# power_amp4.net
KiCad netlist of a schematic drawn in EAGLE
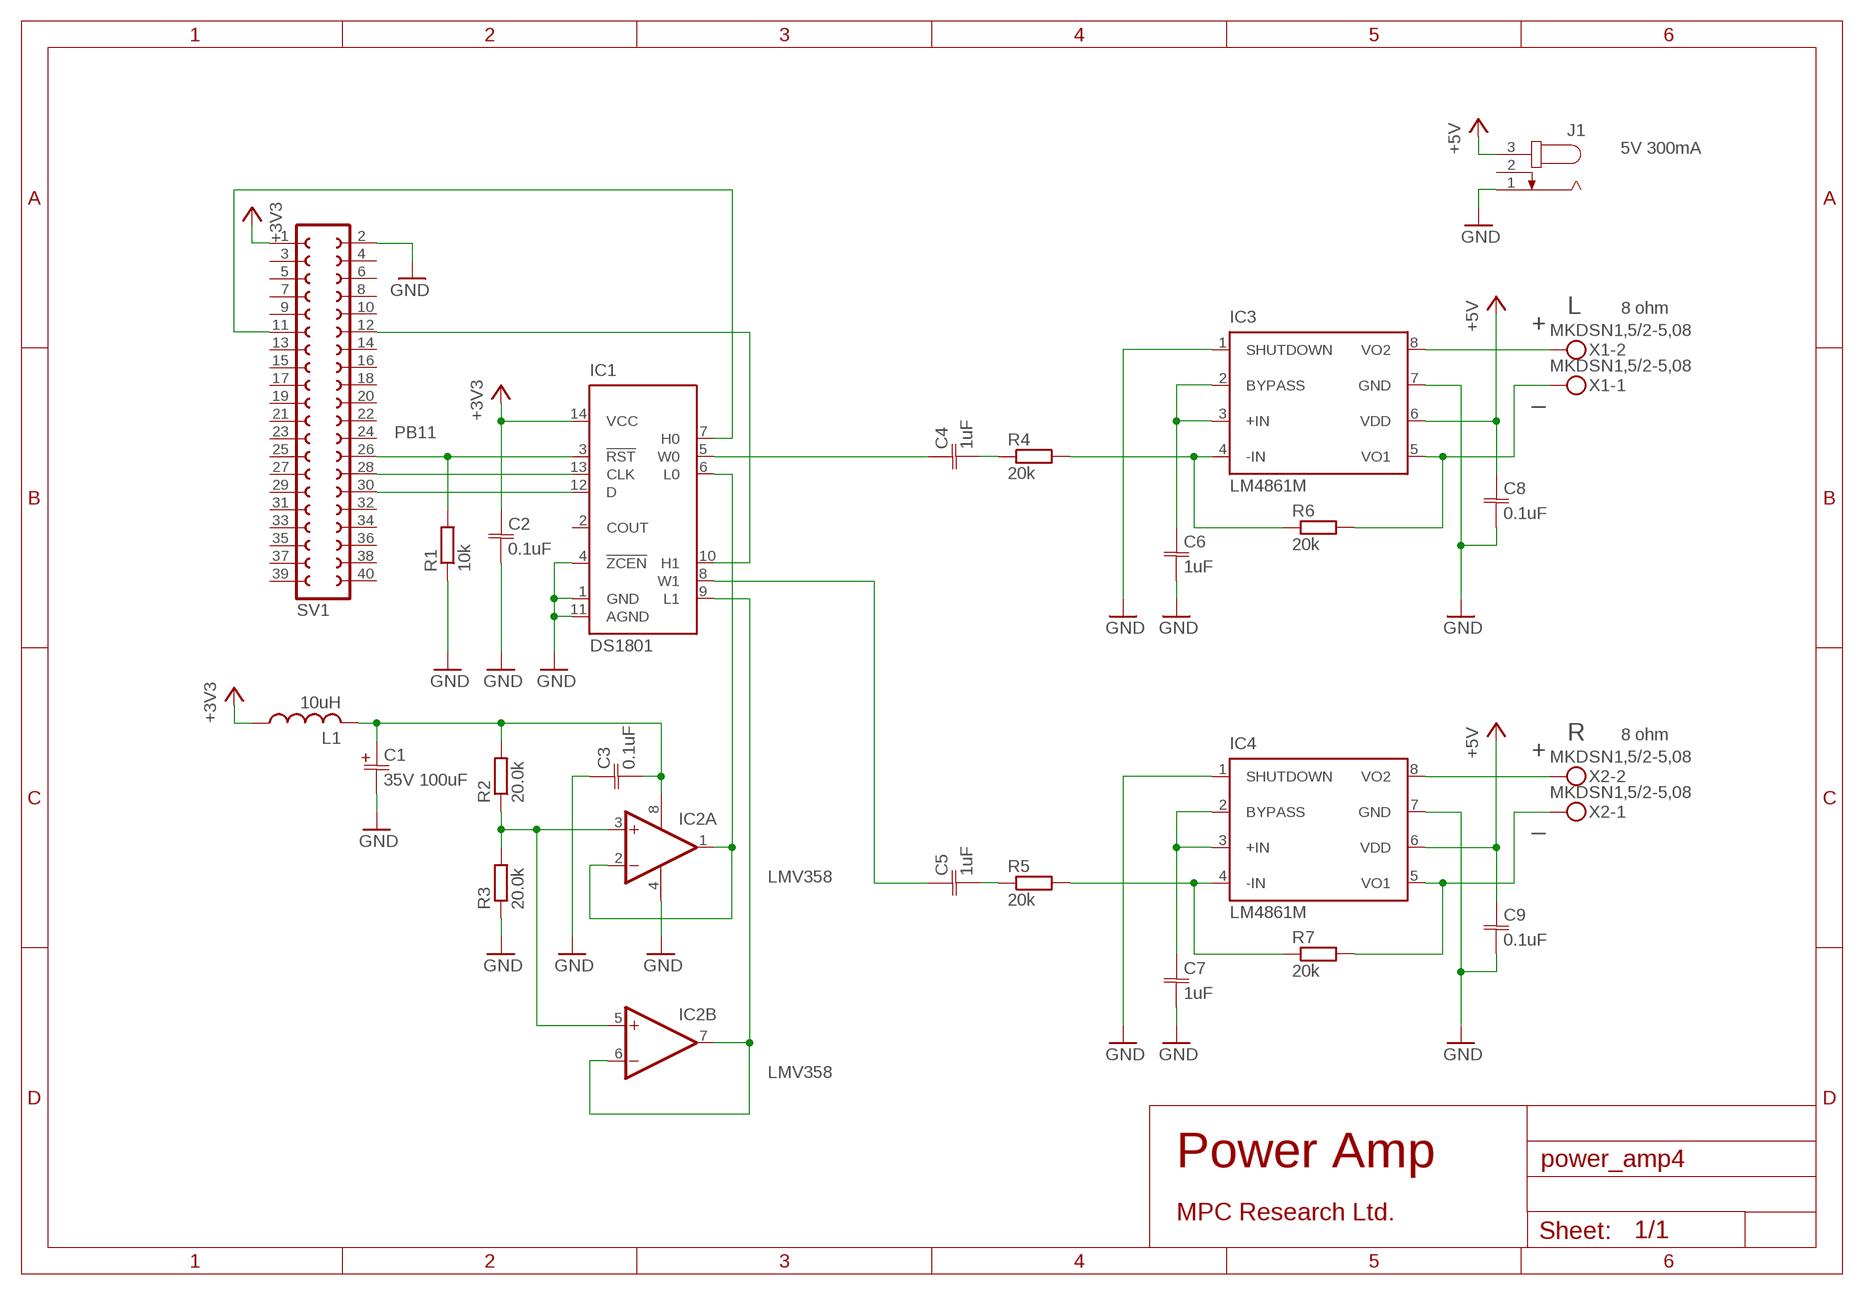
[diagram p0: schematic, sheet 1]

(export (version "E")
  (design (tool "Eeschema 10.0.6"))
  (components
    (comp (ref "C1")
      (value "35V 100uF")
      (footprint "eagle-import:E2,5-5")
      (libsource (lib "eagle-import") (part "CPOL-JIS"))
    )
    (comp (ref "C2")
      (value "0.1uF")
      (footprint "eagle-import:C050-024X044")
      (libsource (lib "eagle-import") (part "C-JIS050-024X044"))
    )
    (comp (ref "C3")
      (value "0.1uF")
      (footprint "eagle-import:C050-024X044")
      (libsource (lib "eagle-import") (part "C-JIS050-024X044"))
    )
    (comp (ref "C4")
      (value "1uF")
      (footprint "eagle-import:C050-024X044")
      (libsource (lib "eagle-import") (part "C-JIS050-024X044"))
    )
    (comp (ref "C5")
      (value "1uF")
      (footprint "eagle-import:C050-024X044")
      (libsource (lib "eagle-import") (part "C-JIS050-024X044"))
    )
    (comp (ref "C6")
      (value "1uF")
      (footprint "eagle-import:C050-024X044")
      (libsource (lib "eagle-import") (part "C-JIS050-024X044"))
    )
    (comp (ref "C7")
      (value "1uF")
      (footprint "eagle-import:C050-024X044")
      (libsource (lib "eagle-import") (part "C-JIS050-024X044"))
    )
    (comp (ref "C8")
      (value "0.1uF")
      (footprint "eagle-import:C050-024X044")
      (libsource (lib "eagle-import") (part "C-JIS050-024X044"))
    )
    (comp (ref "C9")
      (value "0.1uF")
      (footprint "eagle-import:C050-024X044")
      (libsource (lib "eagle-import") (part "C-JIS050-024X044"))
    )
    (comp (ref "IC1")
      (value "DS1801")
      (footprint "eagle-import:DIL14")
      (libsource (lib "eagle-import") (part "DS1801"))
    )
    (comp (ref "IC2")
      (value "LMV358")
      (footprint "eagle-import:SO08")
      (libsource (lib "eagle-import") (part "LMV358?M"))
    )
    (comp (ref "IC3")
      (value "LM4861M")
      (footprint "eagle-import:SO-08")
      (libsource (lib "eagle-import") (part "LM4861M"))
    )
    (comp (ref "IC4")
      (value "LM4861M")
      (footprint "eagle-import:SO-08")
      (libsource (lib "eagle-import") (part "LM4861M"))
    )
    (comp (ref "J1")
      (value "JACK-PLUG0")
      (footprint "eagle-import:SPC4077")
      (libsource (lib "eagle-import") (part "JACK-PLUG0"))
    )
    (comp (ref "L1")
      (value "10uH")
      (footprint "eagle-import:0207_10")
      (libsource (lib "eagle-import") (part "L-US0207/10"))
    )
    (comp (ref "R1")
      (value "10k")
      (footprint "eagle-import:0207_10")
      (libsource (lib "eagle-import") (part "R-EU_0207/10"))
    )
    (comp (ref "R2")
      (value "20.0k")
      (footprint "eagle-import:0207_10")
      (libsource (lib "eagle-import") (part "R-EU_0207/10"))
    )
    (comp (ref "R3")
      (value "20.0k")
      (footprint "eagle-import:0207_10")
      (libsource (lib "eagle-import") (part "R-EU_0207/10"))
    )
    (comp (ref "R4")
      (value "20k")
      (footprint "eagle-import:0207_10")
      (libsource (lib "eagle-import") (part "R-EU_0207/10"))
    )
    (comp (ref "R5")
      (value "20k")
      (footprint "eagle-import:0207_10")
      (libsource (lib "eagle-import") (part "R-EU_0207/10"))
    )
    (comp (ref "R6")
      (value "20k")
      (footprint "eagle-import:0207_10")
      (libsource (lib "eagle-import") (part "R-EU_0207/10"))
    )
    (comp (ref "R7")
      (value "20k")
      (footprint "eagle-import:0207_10")
      (libsource (lib "eagle-import") (part "R-EU_0207/10"))
    )
    (comp (ref "SV1")
      (value "FE20-2")
      (footprint "eagle-import:FE20-2")
      (libsource (lib "eagle-import") (part "FE20-2"))
    )
    (comp (ref "X1")
      (value "MKDSN1,5/2-5,08")
      (footprint "eagle-import:MKDSN1,5_2-5,08")
      (fields (field (name "MPN") "MKDSN 1,5/2-5.08"))
      (libsource (lib "eagle-import") (part "MKDSN1,5/2-5,08"))
    )
    (comp (ref "X2")
      (value "MKDSN1,5/2-5,08")
      (footprint "eagle-import:MKDSN1,5_2-5,08")
      (fields (field (name "MPN") "MKDSN 1,5/2-5.08"))
      (libsource (lib "eagle-import") (part "MKDSN1,5/2-5,08"))
    )
  )
  (nets
    (net (code "1") (name "+3V3") (class "Default")
      (node (ref "C2") (pin "1") (pinfunction "1_1") (pintype "passive"))
      (node (ref "IC1") (pin "14") (pinfunction "VCC_14") (pintype "power_in"))
      (node (ref "L1") (pin "1") (pinfunction "1_1") (pintype "passive"))
      (node (ref "SV1") (pin "1") (pinfunction "1_1") (pintype "passive"))
    )
    (net (code "2") (name "+5V") (class "Default")
      (node (ref "C8") (pin "1") (pinfunction "1_1") (pintype "passive"))
      (node (ref "C9") (pin "1") (pinfunction "1_1") (pintype "passive"))
      (node (ref "IC3") (pin "6") (pinfunction "VDD_6") (pintype "power_in"))
      (node (ref "IC4") (pin "6") (pinfunction "VDD_6") (pintype "power_in"))
      (node (ref "J1") (pin "3") (pinfunction "3_3") (pintype "passive"))
    )
    (net (code "3") (name "GND") (class "Default")
      (node (ref "C1") (pin "-") (pinfunction "-_-") (pintype "passive"))
      (node (ref "C2") (pin "2") (pinfunction "2_2") (pintype "passive"))
      (node (ref "C3") (pin "1") (pinfunction "1_1") (pintype "passive"))
      (node (ref "C6") (pin "2") (pinfunction "2_2") (pintype "passive"))
      (node (ref "C7") (pin "2") (pinfunction "2_2") (pintype "passive"))
      (node (ref "C8") (pin "2") (pinfunction "2_2") (pintype "passive"))
      (node (ref "C9") (pin "2") (pinfunction "2_2") (pintype "passive"))
      (node (ref "IC1") (pin "1") (pinfunction "GND_1") (pintype "power_in"))
      (node (ref "IC1") (pin "11") (pinfunction "AGND_11") (pintype "power_in"))
      (node (ref "IC1") (pin "4") (pinfunction "~{ZCEN}_4") (pintype "input"))
      (node (ref "IC2") (pin "4") (pinfunction "V-_4") (pintype "power_in"))
      (node (ref "IC3") (pin "1") (pinfunction "SHUTDOWN_1") (pintype "input"))
      (node (ref "IC3") (pin "7") (pinfunction "GND_7") (pintype "power_in"))
      (node (ref "IC4") (pin "1") (pinfunction "SHUTDOWN_1") (pintype "input"))
      (node (ref "IC4") (pin "7") (pinfunction "GND_7") (pintype "power_in"))
      (node (ref "J1") (pin "1") (pinfunction "1_1") (pintype "passive"))
      (node (ref "R1") (pin "1") (pinfunction "1_1") (pintype "passive"))
      (node (ref "R3") (pin "1") (pinfunction "1_1") (pintype "passive"))
      (node (ref "SV1") (pin "2") (pinfunction "2_2") (pintype "passive"))
    )
    (net (code "4") (name "Net-(C4-Pad2)") (class "Default")
      (node (ref "C4") (pin "2") (pinfunction "2_2") (pintype "passive"))
      (node (ref "R4") (pin "1") (pinfunction "1_1") (pintype "passive"))
    )
    (net (code "5") (name "Net-(C5-Pad2)") (class "Default")
      (node (ref "C5") (pin "2") (pinfunction "2_2") (pintype "passive"))
      (node (ref "R5") (pin "1") (pinfunction "1_1") (pintype "passive"))
    )
    (net (code "6") (name "Net-(IC1-CLK)") (class "Default")
      (node (ref "IC1") (pin "13") (pinfunction "CLK_13") (pintype "input"))
      (node (ref "SV1") (pin "28") (pinfunction "28_28") (pintype "passive"))
    )
    (net (code "7") (name "Net-(IC1-D)") (class "Default")
      (node (ref "IC1") (pin "12") (pinfunction "D_12") (pintype "input"))
      (node (ref "SV1") (pin "30") (pinfunction "30_30") (pintype "passive"))
    )
    (net (code "8") (name "Net-(IC1-H0)") (class "Default")
      (node (ref "IC1") (pin "7") (pinfunction "H0_7") (pintype "passive"))
      (node (ref "SV1") (pin "11") (pinfunction "11_11") (pintype "passive"))
    )
    (net (code "9") (name "Net-(IC1-H1)") (class "Default")
      (node (ref "IC1") (pin "10") (pinfunction "H1_10") (pintype "passive"))
      (node (ref "SV1") (pin "12") (pinfunction "12_12") (pintype "passive"))
    )
    (net (code "10") (name "Net-(IC1-L0)") (class "Default")
      (node (ref "IC1") (pin "6") (pinfunction "L0_6") (pintype "passive"))
      (node (ref "IC2") (pin "1") (pinfunction "OUT_1") (pintype "output"))
      (node (ref "IC2") (pin "2") (pinfunction "-IN_2") (pintype "input"))
    )
    (net (code "11") (name "Net-(IC1-L1)") (class "Default")
      (node (ref "IC1") (pin "9") (pinfunction "L1_9") (pintype "passive"))
      (node (ref "IC2") (pin "6") (pinfunction "-IN_6") (pintype "input"))
      (node (ref "IC2") (pin "7") (pinfunction "OUT_7") (pintype "output"))
    )
    (net (code "12") (name "Net-(IC1-W0)") (class "Default")
      (node (ref "C4") (pin "1") (pinfunction "1_1") (pintype "passive"))
      (node (ref "IC1") (pin "5") (pinfunction "W0_5") (pintype "passive"))
    )
    (net (code "13") (name "Net-(IC1-W1)") (class "Default")
      (node (ref "C5") (pin "1") (pinfunction "1_1") (pintype "passive"))
      (node (ref "IC1") (pin "8") (pinfunction "W1_8") (pintype "passive"))
    )
    (net (code "14") (name "Net-(IC1-~{RST})") (class "Default")
      (node (ref "IC1") (pin "3") (pinfunction "~{RST}_3") (pintype "input"))
      (node (ref "R1") (pin "2") (pinfunction "2_2") (pintype "passive"))
      (node (ref "SV1") (pin "26") (pinfunction "26_26") (pintype "passive"))
    )
    (net (code "15") (name "Net-(IC2A-+IN)") (class "Default")
      (node (ref "IC2") (pin "3") (pinfunction "+IN_3") (pintype "input"))
      (node (ref "IC2") (pin "5") (pinfunction "+IN_5") (pintype "input"))
      (node (ref "R2") (pin "1") (pinfunction "1_1") (pintype "passive"))
      (node (ref "R3") (pin "2") (pinfunction "2_2") (pintype "passive"))
    )
    (net (code "16") (name "Net-(IC2C-V+)") (class "Default")
      (node (ref "C1") (pin "+") (pinfunction "+_+") (pintype "passive"))
      (node (ref "C3") (pin "2") (pinfunction "2_2") (pintype "passive"))
      (node (ref "IC2") (pin "8") (pinfunction "V+_8") (pintype "power_in"))
      (node (ref "L1") (pin "2") (pinfunction "2_2") (pintype "passive"))
      (node (ref "R2") (pin "2") (pinfunction "2_2") (pintype "passive"))
    )
    (net (code "17") (name "Net-(IC3-+IN)") (class "Default")
      (node (ref "C6") (pin "1") (pinfunction "1_1") (pintype "passive"))
      (node (ref "IC3") (pin "2") (pinfunction "BYPASS_2") (pintype "passive"))
      (node (ref "IC3") (pin "3") (pinfunction "+IN_3") (pintype "input"))
    )
    (net (code "18") (name "Net-(IC3--IN)") (class "Default")
      (node (ref "IC3") (pin "4") (pinfunction "-IN_4") (pintype "input"))
      (node (ref "R4") (pin "2") (pinfunction "2_2") (pintype "passive"))
      (node (ref "R6") (pin "1") (pinfunction "1_1") (pintype "passive"))
    )
    (net (code "19") (name "Net-(IC3-VO1)") (class "Default")
      (node (ref "IC3") (pin "5") (pinfunction "VO1_5") (pintype "output"))
      (node (ref "R6") (pin "2") (pinfunction "2_2") (pintype "passive"))
      (node (ref "X1") (pin "1") (pinfunction "KL_1") (pintype "passive"))
    )
    (net (code "20") (name "Net-(IC3-VO2)") (class "Default")
      (node (ref "IC3") (pin "8") (pinfunction "VO2_8") (pintype "output"))
      (node (ref "X1") (pin "2") (pinfunction "KL_2") (pintype "passive"))
    )
    (net (code "21") (name "Net-(IC4-+IN)") (class "Default")
      (node (ref "C7") (pin "1") (pinfunction "1_1") (pintype "passive"))
      (node (ref "IC4") (pin "2") (pinfunction "BYPASS_2") (pintype "passive"))
      (node (ref "IC4") (pin "3") (pinfunction "+IN_3") (pintype "input"))
    )
    (net (code "22") (name "Net-(IC4--IN)") (class "Default")
      (node (ref "IC4") (pin "4") (pinfunction "-IN_4") (pintype "input"))
      (node (ref "R5") (pin "2") (pinfunction "2_2") (pintype "passive"))
      (node (ref "R7") (pin "1") (pinfunction "1_1") (pintype "passive"))
    )
    (net (code "23") (name "Net-(IC4-VO1)") (class "Default")
      (node (ref "IC4") (pin "5") (pinfunction "VO1_5") (pintype "output"))
      (node (ref "R7") (pin "2") (pinfunction "2_2") (pintype "passive"))
      (node (ref "X2") (pin "1") (pinfunction "KL_1") (pintype "passive"))
    )
    (net (code "24") (name "Net-(IC4-VO2)") (class "Default")
      (node (ref "IC4") (pin "8") (pinfunction "VO2_8") (pintype "output"))
      (node (ref "X2") (pin "2") (pinfunction "KL_2") (pintype "passive"))
    )
    (net (code "25") (name "unconnected-(IC1-COUT-Pad2)") (class "Default")
      (node (ref "IC1") (pin "2") (pinfunction "COUT_2") (pintype "output"))
    )
    (net (code "26") (name "unconnected-(J1-Pad2)") (class "Default")
      (node (ref "J1") (pin "2") (pinfunction "2_2") (pintype "passive"))
    )
    (net (code "27") (name "unconnected-(SV1-Pad3)") (class "Default")
      (node (ref "SV1") (pin "3") (pinfunction "3_3") (pintype "passive"))
    )
    (net (code "28") (name "unconnected-(SV1-Pad4)") (class "Default")
      (node (ref "SV1") (pin "4") (pinfunction "4_4") (pintype "passive"))
    )
    (net (code "29") (name "unconnected-(SV1-Pad5)") (class "Default")
      (node (ref "SV1") (pin "5") (pinfunction "5_5") (pintype "passive"))
    )
    (net (code "30") (name "unconnected-(SV1-Pad6)") (class "Default")
      (node (ref "SV1") (pin "6") (pinfunction "6_6") (pintype "passive"))
    )
    (net (code "31") (name "unconnected-(SV1-Pad7)") (class "Default")
      (node (ref "SV1") (pin "7") (pinfunction "7_7") (pintype "passive"))
    )
    (net (code "32") (name "unconnected-(SV1-Pad8)") (class "Default")
      (node (ref "SV1") (pin "8") (pinfunction "8_8") (pintype "passive"))
    )
    (net (code "33") (name "unconnected-(SV1-Pad9)") (class "Default")
      (node (ref "SV1") (pin "9") (pinfunction "9_9") (pintype "passive"))
    )
    (net (code "34") (name "unconnected-(SV1-Pad10)") (class "Default")
      (node (ref "SV1") (pin "10") (pinfunction "10_10") (pintype "passive"))
    )
    (net (code "35") (name "unconnected-(SV1-Pad13)") (class "Default")
      (node (ref "SV1") (pin "13") (pinfunction "13_13") (pintype "passive"))
    )
    (net (code "36") (name "unconnected-(SV1-Pad14)") (class "Default")
      (node (ref "SV1") (pin "14") (pinfunction "14_14") (pintype "passive"))
    )
    (net (code "37") (name "unconnected-(SV1-Pad15)") (class "Default")
      (node (ref "SV1") (pin "15") (pinfunction "15_15") (pintype "passive"))
    )
    (net (code "38") (name "unconnected-(SV1-Pad16)") (class "Default")
      (node (ref "SV1") (pin "16") (pinfunction "16_16") (pintype "passive"))
    )
    (net (code "39") (name "unconnected-(SV1-Pad17)") (class "Default")
      (node (ref "SV1") (pin "17") (pinfunction "17_17") (pintype "passive"))
    )
    (net (code "40") (name "unconnected-(SV1-Pad18)") (class "Default")
      (node (ref "SV1") (pin "18") (pinfunction "18_18") (pintype "passive"))
    )
    (net (code "41") (name "unconnected-(SV1-Pad19)") (class "Default")
      (node (ref "SV1") (pin "19") (pinfunction "19_19") (pintype "passive"))
    )
    (net (code "42") (name "unconnected-(SV1-Pad20)") (class "Default")
      (node (ref "SV1") (pin "20") (pinfunction "20_20") (pintype "passive"))
    )
    (net (code "43") (name "unconnected-(SV1-Pad21)") (class "Default")
      (node (ref "SV1") (pin "21") (pinfunction "21_21") (pintype "passive"))
    )
    (net (code "44") (name "unconnected-(SV1-Pad22)") (class "Default")
      (node (ref "SV1") (pin "22") (pinfunction "22_22") (pintype "passive"))
    )
    (net (code "45") (name "unconnected-(SV1-Pad23)") (class "Default")
      (node (ref "SV1") (pin "23") (pinfunction "23_23") (pintype "passive"))
    )
    (net (code "46") (name "unconnected-(SV1-Pad24)") (class "Default")
      (node (ref "SV1") (pin "24") (pinfunction "24_24") (pintype "passive"))
    )
    (net (code "47") (name "unconnected-(SV1-Pad25)") (class "Default")
      (node (ref "SV1") (pin "25") (pinfunction "25_25") (pintype "passive"))
    )
    (net (code "48") (name "unconnected-(SV1-Pad27)") (class "Default")
      (node (ref "SV1") (pin "27") (pinfunction "27_27") (pintype "passive"))
    )
    (net (code "49") (name "unconnected-(SV1-Pad29)") (class "Default")
      (node (ref "SV1") (pin "29") (pinfunction "29_29") (pintype "passive"))
    )
    (net (code "50") (name "unconnected-(SV1-Pad31)") (class "Default")
      (node (ref "SV1") (pin "31") (pinfunction "31_31") (pintype "passive"))
    )
    (net (code "51") (name "unconnected-(SV1-Pad32)") (class "Default")
      (node (ref "SV1") (pin "32") (pinfunction "32_32") (pintype "passive"))
    )
    (net (code "52") (name "unconnected-(SV1-Pad33)") (class "Default")
      (node (ref "SV1") (pin "33") (pinfunction "33_33") (pintype "passive"))
    )
    (net (code "53") (name "unconnected-(SV1-Pad34)") (class "Default")
      (node (ref "SV1") (pin "34") (pinfunction "34_34") (pintype "passive"))
    )
    (net (code "54") (name "unconnected-(SV1-Pad35)") (class "Default")
      (node (ref "SV1") (pin "35") (pinfunction "35_35") (pintype "passive"))
    )
    (net (code "55") (name "unconnected-(SV1-Pad36)") (class "Default")
      (node (ref "SV1") (pin "36") (pinfunction "36_36") (pintype "passive"))
    )
    (net (code "56") (name "unconnected-(SV1-Pad37)") (class "Default")
      (node (ref "SV1") (pin "37") (pinfunction "37_37") (pintype "passive"))
    )
    (net (code "57") (name "unconnected-(SV1-Pad38)") (class "Default")
      (node (ref "SV1") (pin "38") (pinfunction "38_38") (pintype "passive"))
    )
    (net (code "58") (name "unconnected-(SV1-Pad39)") (class "Default")
      (node (ref "SV1") (pin "39") (pinfunction "39_39") (pintype "passive"))
    )
    (net (code "59") (name "unconnected-(SV1-Pad40)") (class "Default")
      (node (ref "SV1") (pin "40") (pinfunction "40_40") (pintype "passive"))
    )
  )
)
